# Placa_CLP_2021-08-01_15-29-45.net
KiCad netlist of a schematic drawn in EasyEDA
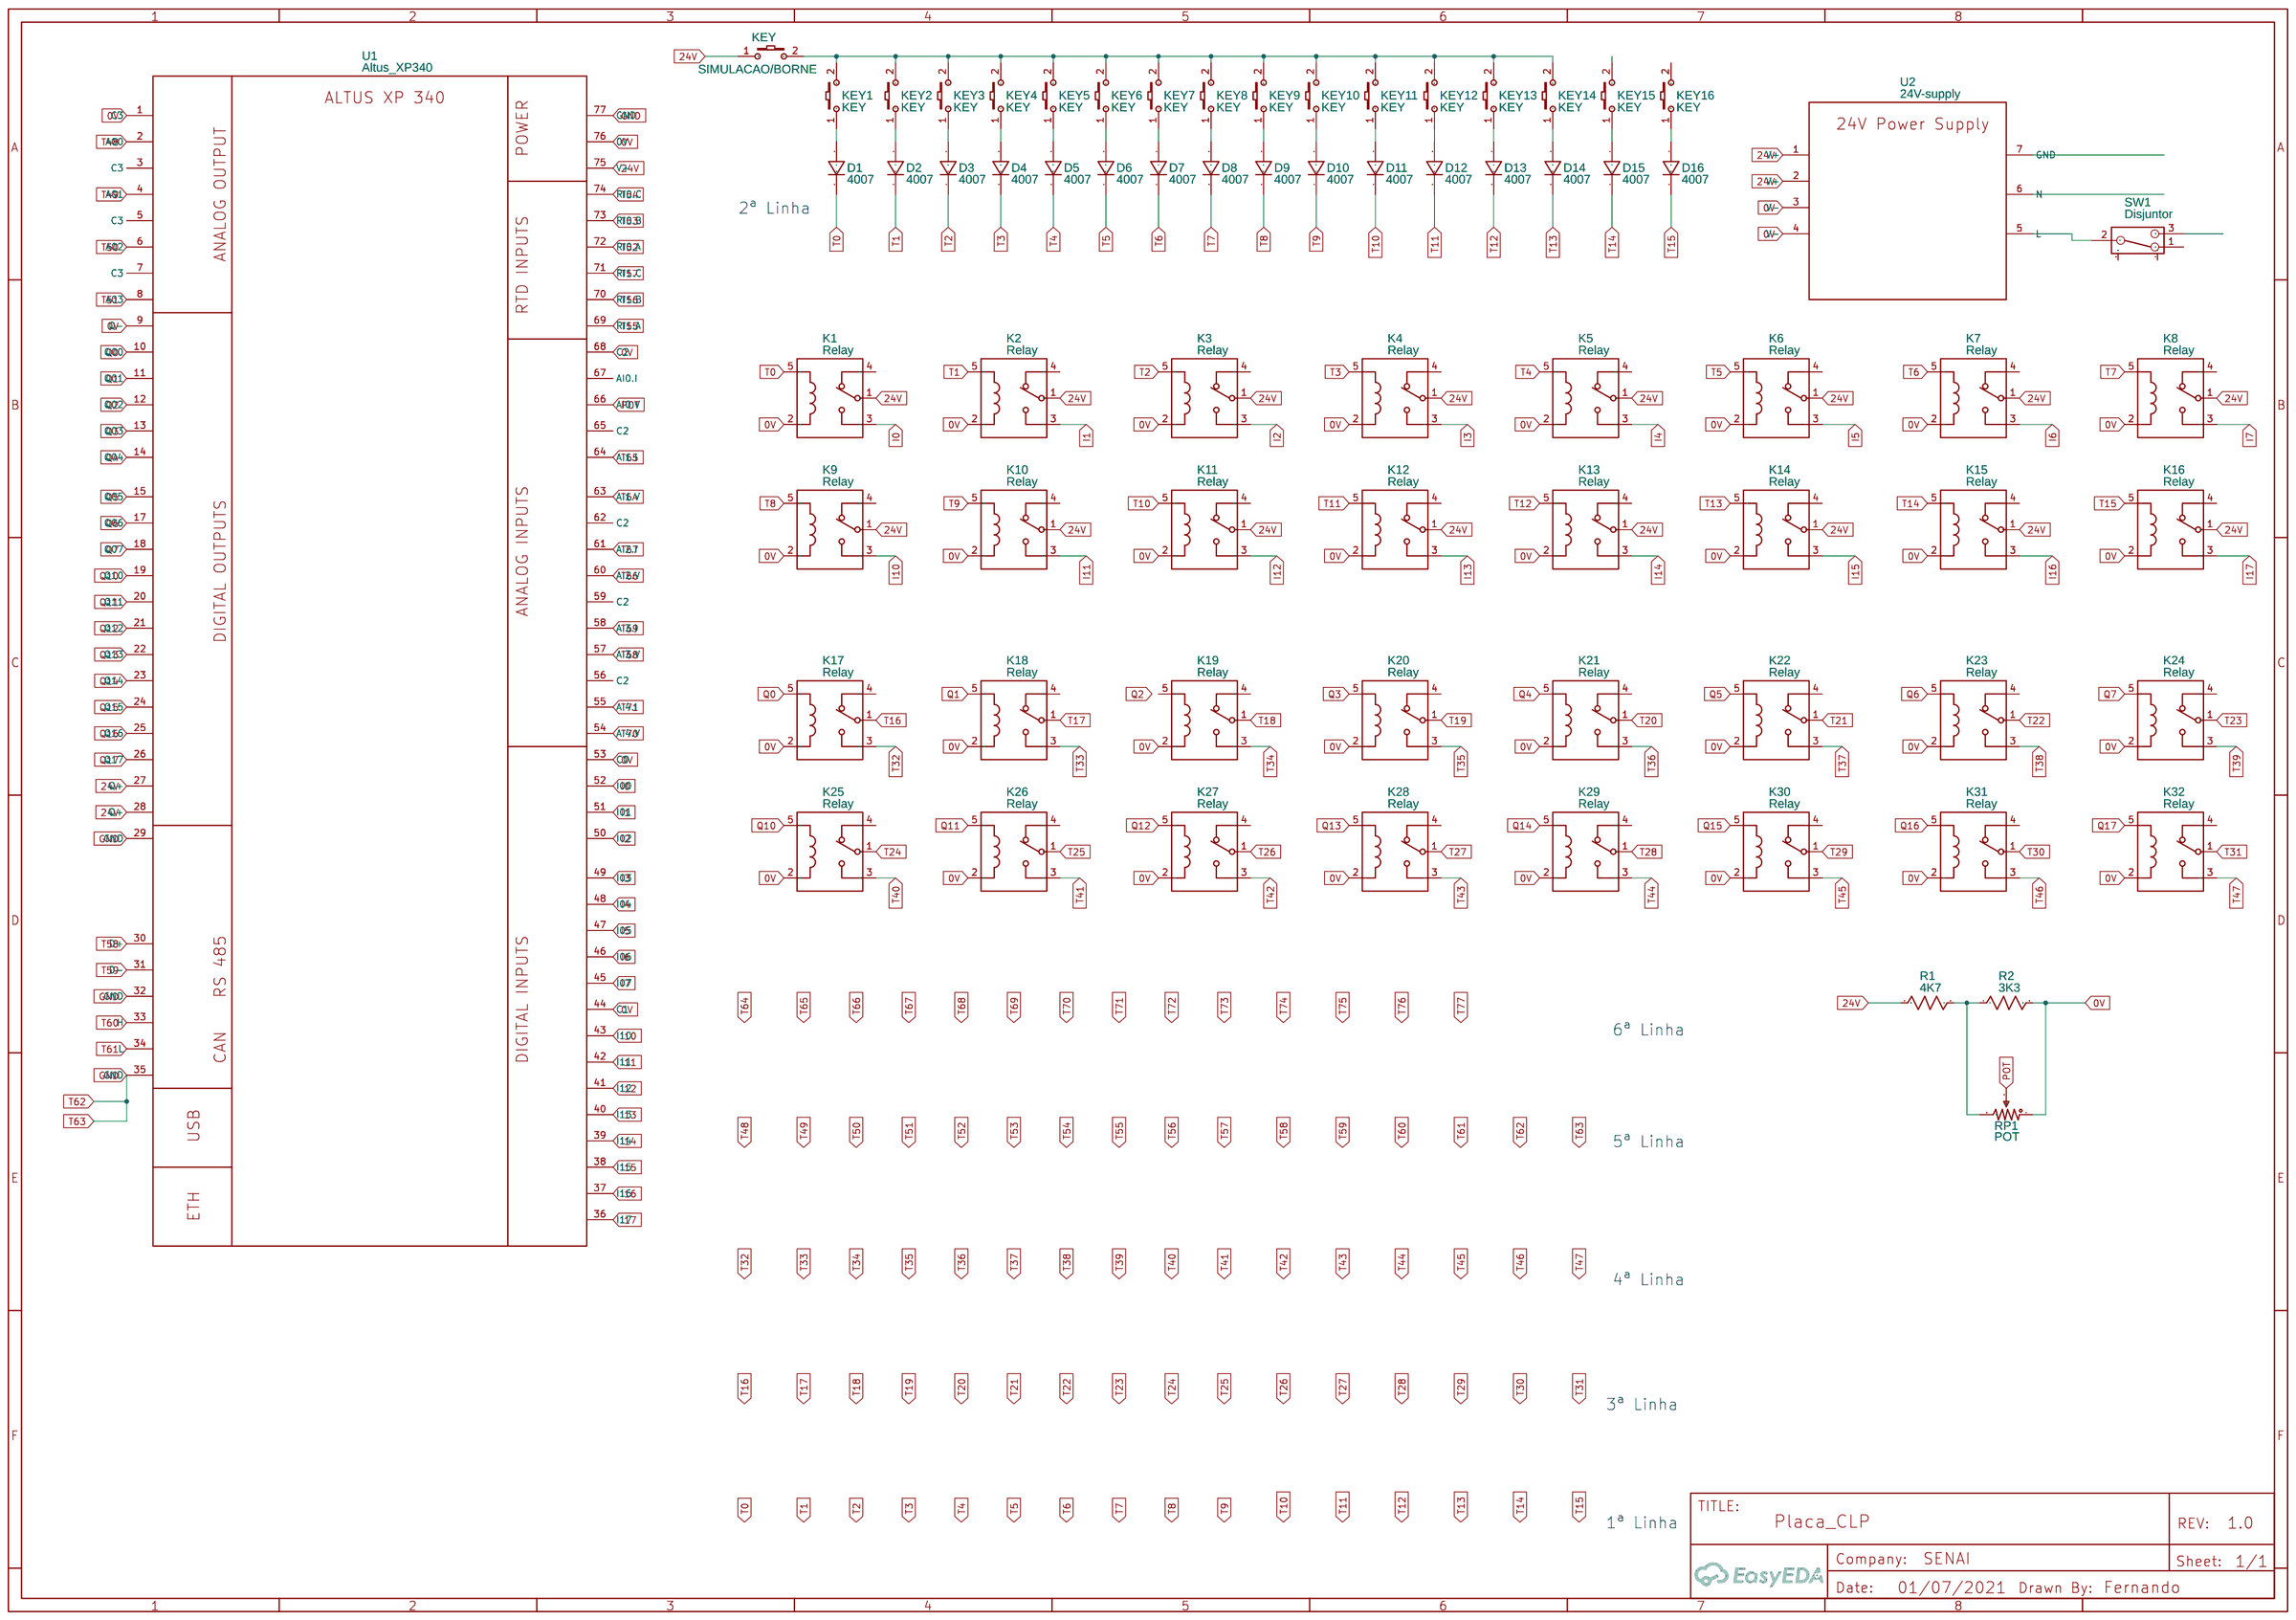
[diagram p0: schematic sheet]

(export (version "E")
  (design (tool "Eeschema 10.0.6"))
  (components
    (comp (ref "D1")
      (value "4007")
      (fields (field (name "BOM_Manufacturer Part") "1N4007") (field (name "BOM_Supplier Part") "C106903"))
      (libsource (lib "") (part "1N4007"))
    )
    (comp (ref "D2")
      (value "4007")
      (fields (field (name "BOM_Manufacturer Part") "1N4007") (field (name "BOM_Supplier Part") "C106903"))
      (libsource (lib "") (part "1N4007"))
    )
    (comp (ref "D3")
      (value "4007")
      (fields (field (name "BOM_Manufacturer Part") "1N4007") (field (name "BOM_Supplier Part") "C106903"))
      (libsource (lib "") (part "1N4007"))
    )
    (comp (ref "D4")
      (value "4007")
      (fields (field (name "BOM_Manufacturer Part") "1N4007") (field (name "BOM_Supplier Part") "C106903"))
      (libsource (lib "") (part "1N4007"))
    )
    (comp (ref "D5")
      (value "4007")
      (fields (field (name "BOM_Manufacturer Part") "1N4007") (field (name "BOM_Supplier Part") "C106903"))
      (libsource (lib "") (part "1N4007"))
    )
    (comp (ref "D6")
      (value "4007")
      (fields (field (name "BOM_Manufacturer Part") "1N4007") (field (name "BOM_Supplier Part") "C106903"))
      (libsource (lib "") (part "1N4007"))
    )
    (comp (ref "D7")
      (value "4007")
      (fields (field (name "BOM_Manufacturer Part") "1N4007") (field (name "BOM_Supplier Part") "C106903"))
      (libsource (lib "") (part "1N4007"))
    )
    (comp (ref "D8")
      (value "4007")
      (fields (field (name "BOM_Manufacturer Part") "1N4007") (field (name "BOM_Supplier Part") "C106903"))
      (libsource (lib "") (part "1N4007"))
    )
    (comp (ref "D9")
      (value "4007")
      (fields (field (name "BOM_Manufacturer Part") "1N4007") (field (name "BOM_Supplier Part") "C106903"))
      (libsource (lib "") (part "1N4007"))
    )
    (comp (ref "D10")
      (value "4007")
      (fields (field (name "BOM_Manufacturer Part") "1N4007") (field (name "BOM_Supplier Part") "C106903"))
      (libsource (lib "") (part "1N4007"))
    )
    (comp (ref "D11")
      (value "4007")
      (fields (field (name "BOM_Manufacturer Part") "1N4007") (field (name "BOM_Supplier Part") "C106903"))
      (libsource (lib "") (part "1N4007"))
    )
    (comp (ref "D12")
      (value "4007")
      (fields (field (name "BOM_Manufacturer Part") "1N4007") (field (name "BOM_Supplier Part") "C106903"))
      (libsource (lib "") (part "1N4007"))
    )
    (comp (ref "D13")
      (value "4007")
      (fields (field (name "BOM_Manufacturer Part") "1N4007") (field (name "BOM_Supplier Part") "C106903"))
      (libsource (lib "") (part "1N4007"))
    )
    (comp (ref "D14")
      (value "4007")
      (fields (field (name "BOM_Manufacturer Part") "1N4007") (field (name "BOM_Supplier Part") "C106903"))
      (libsource (lib "") (part "1N4007"))
    )
    (comp (ref "D15")
      (value "4007")
      (fields (field (name "BOM_Manufacturer Part") "1N4007") (field (name "BOM_Supplier Part") "C106903"))
      (libsource (lib "") (part "1N4007"))
    )
    (comp (ref "D16")
      (value "4007")
      (fields (field (name "BOM_Manufacturer Part") "1N4007") (field (name "BOM_Supplier Part") "C106903"))
      (libsource (lib "") (part "1N4007"))
    )
    (comp (ref "K1")
      (value "Relay")
      (fields
        (field (name "BOM_Manufacturer Part") "RelayHT3F-12VDC-SHG")
        (field (name "BOM_Supplier Part") "C22022")
      )
      (libsource (lib "") (part "RelayHT3F-12VDC-SHG"))
    )
    (comp (ref "K2")
      (value "Relay")
      (fields
        (field (name "BOM_Manufacturer Part") "RelayHT3F-12VDC-SHG")
        (field (name "BOM_Supplier Part") "C22022")
      )
      (libsource (lib "") (part "RelayHT3F-12VDC-SHG"))
    )
    (comp (ref "K3")
      (value "Relay")
      (fields
        (field (name "BOM_Manufacturer Part") "RelayHT3F-12VDC-SHG")
        (field (name "BOM_Supplier Part") "C22022")
      )
      (libsource (lib "") (part "RelayHT3F-12VDC-SHG"))
    )
    (comp (ref "K4")
      (value "Relay")
      (fields
        (field (name "BOM_Manufacturer Part") "RelayHT3F-12VDC-SHG")
        (field (name "BOM_Supplier Part") "C22022")
      )
      (libsource (lib "") (part "RelayHT3F-12VDC-SHG"))
    )
    (comp (ref "K5")
      (value "Relay")
      (fields
        (field (name "BOM_Manufacturer Part") "RelayHT3F-12VDC-SHG")
        (field (name "BOM_Supplier Part") "C22022")
      )
      (libsource (lib "") (part "RelayHT3F-12VDC-SHG"))
    )
    (comp (ref "K6")
      (value "Relay")
      (fields
        (field (name "BOM_Manufacturer Part") "RelayHT3F-12VDC-SHG")
        (field (name "BOM_Supplier Part") "C22022")
      )
      (libsource (lib "") (part "RelayHT3F-12VDC-SHG"))
    )
    (comp (ref "K7")
      (value "Relay")
      (fields
        (field (name "BOM_Manufacturer Part") "RelayHT3F-12VDC-SHG")
        (field (name "BOM_Supplier Part") "C22022")
      )
      (libsource (lib "") (part "RelayHT3F-12VDC-SHG"))
    )
    (comp (ref "K8")
      (value "Relay")
      (fields
        (field (name "BOM_Manufacturer Part") "RelayHT3F-12VDC-SHG")
        (field (name "BOM_Supplier Part") "C22022")
      )
      (libsource (lib "") (part "RelayHT3F-12VDC-SHG"))
    )
    (comp (ref "K9")
      (value "Relay")
      (fields
        (field (name "BOM_Manufacturer Part") "RelayHT3F-12VDC-SHG")
        (field (name "BOM_Supplier Part") "C22022")
      )
      (libsource (lib "") (part "RelayHT3F-12VDC-SHG"))
    )
    (comp (ref "K10")
      (value "Relay")
      (fields
        (field (name "BOM_Manufacturer Part") "RelayHT3F-12VDC-SHG")
        (field (name "BOM_Supplier Part") "C22022")
      )
      (libsource (lib "") (part "RelayHT3F-12VDC-SHG"))
    )
    (comp (ref "K11")
      (value "Relay")
      (fields
        (field (name "BOM_Manufacturer Part") "RelayHT3F-12VDC-SHG")
        (field (name "BOM_Supplier Part") "C22022")
      )
      (libsource (lib "") (part "RelayHT3F-12VDC-SHG"))
    )
    (comp (ref "K12")
      (value "Relay")
      (fields
        (field (name "BOM_Manufacturer Part") "RelayHT3F-12VDC-SHG")
        (field (name "BOM_Supplier Part") "C22022")
      )
      (libsource (lib "") (part "RelayHT3F-12VDC-SHG"))
    )
    (comp (ref "K13")
      (value "Relay")
      (fields
        (field (name "BOM_Manufacturer Part") "RelayHT3F-12VDC-SHG")
        (field (name "BOM_Supplier Part") "C22022")
      )
      (libsource (lib "") (part "RelayHT3F-12VDC-SHG"))
    )
    (comp (ref "K14")
      (value "Relay")
      (fields
        (field (name "BOM_Manufacturer Part") "RelayHT3F-12VDC-SHG")
        (field (name "BOM_Supplier Part") "C22022")
      )
      (libsource (lib "") (part "RelayHT3F-12VDC-SHG"))
    )
    (comp (ref "K15")
      (value "Relay")
      (fields
        (field (name "BOM_Manufacturer Part") "RelayHT3F-12VDC-SHG")
        (field (name "BOM_Supplier Part") "C22022")
      )
      (libsource (lib "") (part "RelayHT3F-12VDC-SHG"))
    )
    (comp (ref "K16")
      (value "Relay")
      (fields
        (field (name "BOM_Manufacturer Part") "RelayHT3F-12VDC-SHG")
        (field (name "BOM_Supplier Part") "C22022")
      )
      (libsource (lib "") (part "RelayHT3F-12VDC-SHG"))
    )
    (comp (ref "K17")
      (value "Relay")
      (fields
        (field (name "BOM_Manufacturer Part") "RelayHT3F-12VDC-SHG")
        (field (name "BOM_Supplier Part") "C22022")
      )
      (libsource (lib "") (part "RelayHT3F-12VDC-SHG"))
    )
    (comp (ref "K18")
      (value "Relay")
      (fields
        (field (name "BOM_Manufacturer Part") "RelayHT3F-12VDC-SHG")
        (field (name "BOM_Supplier Part") "C22022")
      )
      (libsource (lib "") (part "RelayHT3F-12VDC-SHG"))
    )
    (comp (ref "K19")
      (value "Relay")
      (fields
        (field (name "BOM_Manufacturer Part") "RelayHT3F-12VDC-SHG")
        (field (name "BOM_Supplier Part") "C22022")
      )
      (libsource (lib "") (part "RelayHT3F-12VDC-SHG"))
    )
    (comp (ref "K20")
      (value "Relay")
      (fields
        (field (name "BOM_Manufacturer Part") "RelayHT3F-12VDC-SHG")
        (field (name "BOM_Supplier Part") "C22022")
      )
      (libsource (lib "") (part "RelayHT3F-12VDC-SHG"))
    )
    (comp (ref "K21")
      (value "Relay")
      (fields
        (field (name "BOM_Manufacturer Part") "RelayHT3F-12VDC-SHG")
        (field (name "BOM_Supplier Part") "C22022")
      )
      (libsource (lib "") (part "RelayHT3F-12VDC-SHG"))
    )
    (comp (ref "K22")
      (value "Relay")
      (fields
        (field (name "BOM_Manufacturer Part") "RelayHT3F-12VDC-SHG")
        (field (name "BOM_Supplier Part") "C22022")
      )
      (libsource (lib "") (part "RelayHT3F-12VDC-SHG"))
    )
    (comp (ref "K23")
      (value "Relay")
      (fields
        (field (name "BOM_Manufacturer Part") "RelayHT3F-12VDC-SHG")
        (field (name "BOM_Supplier Part") "C22022")
      )
      (libsource (lib "") (part "RelayHT3F-12VDC-SHG"))
    )
    (comp (ref "K24")
      (value "Relay")
      (fields
        (field (name "BOM_Manufacturer Part") "RelayHT3F-12VDC-SHG")
        (field (name "BOM_Supplier Part") "C22022")
      )
      (libsource (lib "") (part "RelayHT3F-12VDC-SHG"))
    )
    (comp (ref "K25")
      (value "Relay")
      (fields
        (field (name "BOM_Manufacturer Part") "RelayHT3F-12VDC-SHG")
        (field (name "BOM_Supplier Part") "C22022")
      )
      (libsource (lib "") (part "RelayHT3F-12VDC-SHG"))
    )
    (comp (ref "K26")
      (value "Relay")
      (fields
        (field (name "BOM_Manufacturer Part") "RelayHT3F-12VDC-SHG")
        (field (name "BOM_Supplier Part") "C22022")
      )
      (libsource (lib "") (part "RelayHT3F-12VDC-SHG"))
    )
    (comp (ref "K27")
      (value "Relay")
      (fields
        (field (name "BOM_Manufacturer Part") "RelayHT3F-12VDC-SHG")
        (field (name "BOM_Supplier Part") "C22022")
      )
      (libsource (lib "") (part "RelayHT3F-12VDC-SHG"))
    )
    (comp (ref "K28")
      (value "Relay")
      (fields
        (field (name "BOM_Manufacturer Part") "RelayHT3F-12VDC-SHG")
        (field (name "BOM_Supplier Part") "C22022")
      )
      (libsource (lib "") (part "RelayHT3F-12VDC-SHG"))
    )
    (comp (ref "K29")
      (value "Relay")
      (fields
        (field (name "BOM_Manufacturer Part") "RelayHT3F-12VDC-SHG")
        (field (name "BOM_Supplier Part") "C22022")
      )
      (libsource (lib "") (part "RelayHT3F-12VDC-SHG"))
    )
    (comp (ref "K30")
      (value "Relay")
      (fields
        (field (name "BOM_Manufacturer Part") "RelayHT3F-12VDC-SHG")
        (field (name "BOM_Supplier Part") "C22022")
      )
      (libsource (lib "") (part "RelayHT3F-12VDC-SHG"))
    )
    (comp (ref "K31")
      (value "Relay")
      (fields
        (field (name "BOM_Manufacturer Part") "RelayHT3F-12VDC-SHG")
        (field (name "BOM_Supplier Part") "C22022")
      )
      (libsource (lib "") (part "RelayHT3F-12VDC-SHG"))
    )
    (comp (ref "K32")
      (value "Relay")
      (fields
        (field (name "BOM_Manufacturer Part") "RelayHT3F-12VDC-SHG")
        (field (name "BOM_Supplier Part") "C22022")
      )
      (libsource (lib "") (part "RelayHT3F-12VDC-SHG"))
    )
    (comp (ref "KEY1")
      (value "KEY")
      (fields
        (field (name "BOM_Manufacturer Part") "K2-1107ST-A4SW-06")
        (field (name "BOM_Supplier Part") "C118141")
      )
      (libsource (lib "") (part "K2-3.6×6.1_SMD_1"))
    )
    (comp (ref "KEY2")
      (value "KEY")
      (fields
        (field (name "BOM_Manufacturer Part") "K2-1107ST-A4SW-06")
        (field (name "BOM_Supplier Part") "C118141")
      )
      (libsource (lib "") (part "K2-3.6×6.1_SMD_1"))
    )
    (comp (ref "KEY3")
      (value "KEY")
      (fields
        (field (name "BOM_Manufacturer Part") "K2-1107ST-A4SW-06")
        (field (name "BOM_Supplier Part") "C118141")
      )
      (libsource (lib "") (part "K2-3.6×6.1_SMD_1"))
    )
    (comp (ref "KEY4")
      (value "KEY")
      (fields
        (field (name "BOM_Manufacturer Part") "K2-1107ST-A4SW-06")
        (field (name "BOM_Supplier Part") "C118141")
      )
      (libsource (lib "") (part "K2-3.6×6.1_SMD_1"))
    )
    (comp (ref "KEY5")
      (value "KEY")
      (fields
        (field (name "BOM_Manufacturer Part") "K2-1107ST-A4SW-06")
        (field (name "BOM_Supplier Part") "C118141")
      )
      (libsource (lib "") (part "K2-3.6×6.1_SMD_1"))
    )
    (comp (ref "KEY6")
      (value "KEY")
      (fields
        (field (name "BOM_Manufacturer Part") "K2-1107ST-A4SW-06")
        (field (name "BOM_Supplier Part") "C118141")
      )
      (libsource (lib "") (part "K2-3.6×6.1_SMD_1"))
    )
    (comp (ref "KEY7")
      (value "KEY")
      (fields
        (field (name "BOM_Manufacturer Part") "K2-1107ST-A4SW-06")
        (field (name "BOM_Supplier Part") "C118141")
      )
      (libsource (lib "") (part "K2-3.6×6.1_SMD_1"))
    )
    (comp (ref "KEY8")
      (value "KEY")
      (fields
        (field (name "BOM_Manufacturer Part") "K2-1107ST-A4SW-06")
        (field (name "BOM_Supplier Part") "C118141")
      )
      (libsource (lib "") (part "K2-3.6×6.1_SMD_1"))
    )
    (comp (ref "KEY9")
      (value "KEY")
      (fields
        (field (name "BOM_Manufacturer Part") "K2-1107ST-A4SW-06")
        (field (name "BOM_Supplier Part") "C118141")
      )
      (libsource (lib "") (part "K2-3.6×6.1_SMD_1"))
    )
    (comp (ref "KEY10")
      (value "KEY")
      (fields
        (field (name "BOM_Manufacturer Part") "K2-1107ST-A4SW-06")
        (field (name "BOM_Supplier Part") "C118141")
      )
      (libsource (lib "") (part "K2-3.6×6.1_SMD_1"))
    )
    (comp (ref "KEY11")
      (value "KEY")
      (fields
        (field (name "BOM_Manufacturer Part") "K2-1107ST-A4SW-06")
        (field (name "BOM_Supplier Part") "C118141")
      )
      (libsource (lib "") (part "K2-3.6×6.1_SMD_1"))
    )
    (comp (ref "KEY12")
      (value "KEY")
      (fields
        (field (name "BOM_Manufacturer Part") "K2-1107ST-A4SW-06")
        (field (name "BOM_Supplier Part") "C118141")
      )
      (libsource (lib "") (part "K2-3.6×6.1_SMD_1"))
    )
    (comp (ref "KEY13")
      (value "KEY")
      (fields
        (field (name "BOM_Manufacturer Part") "K2-1107ST-A4SW-06")
        (field (name "BOM_Supplier Part") "C118141")
      )
      (libsource (lib "") (part "K2-3.6×6.1_SMD_1"))
    )
    (comp (ref "KEY14")
      (value "KEY")
      (fields
        (field (name "BOM_Manufacturer Part") "K2-1107ST-A4SW-06")
        (field (name "BOM_Supplier Part") "C118141")
      )
      (libsource (lib "") (part "K2-3.6×6.1_SMD_1"))
    )
    (comp (ref "KEY15")
      (value "KEY")
      (fields
        (field (name "BOM_Manufacturer Part") "K2-1107ST-A4SW-06")
        (field (name "BOM_Supplier Part") "C118141")
      )
      (libsource (lib "") (part "K2-3.6×6.1_SMD_1"))
    )
    (comp (ref "KEY16")
      (value "KEY")
      (fields
        (field (name "BOM_Manufacturer Part") "K2-1107ST-A4SW-06")
        (field (name "BOM_Supplier Part") "C118141")
      )
      (libsource (lib "") (part "K2-3.6×6.1_SMD_1"))
    )
    (comp (ref "R1") (value "4K7") (libsource (lib "") (part "R_0603_US")))
    (comp (ref "R2") (value "3K3") (libsource (lib "") (part "R_0603_US")))
    (comp (ref "RP1") (value "POT") (libsource (lib "") (part "R_3386P_US")))
    (comp (ref "SIMULACAO/BORNE")
      (value "KEY")
      (fields
        (field (name "BOM_Manufacturer Part") "K2-1107ST-A4SW-06")
        (field (name "BOM_Supplier Part") "C118141")
      )
      (libsource (lib "") (part "K2-3.6×6.1_SMD"))
    )
    (comp (ref "SW1")
      (value "Disjuntor")
      (fields
        (field (name "BOM_Manufacturer Part") "SK-12D02-VG5")
        (field (name "BOM_Supplier Part") "C136722")
      )
      (libsource (lib "") (part "SK-12D02-VG5"))
    )
    (comp (ref "U1") (value "Altus_XP340") (libsource (lib "") (part "Altus_XP340")))
    (comp (ref "U2") (value "24V-supply") (libsource (lib "") (part "24V-supply")))
  )
  (nets
    (net (code "1") (name "0V") (class "Default")
      (node (ref "K1") (pin "2") (pinfunction "2_2") (pintype "unspecified"))
      (node (ref "K10") (pin "2") (pinfunction "2_2") (pintype "unspecified"))
      (node (ref "K11") (pin "2") (pinfunction "2_2") (pintype "unspecified"))
      (node (ref "K12") (pin "2") (pinfunction "2_2") (pintype "unspecified"))
      (node (ref "K13") (pin "2") (pinfunction "2_2") (pintype "unspecified"))
      (node (ref "K14") (pin "2") (pinfunction "2_2") (pintype "unspecified"))
      (node (ref "K15") (pin "2") (pinfunction "2_2") (pintype "unspecified"))
      (node (ref "K16") (pin "2") (pinfunction "2_2") (pintype "unspecified"))
      (node (ref "K17") (pin "2") (pinfunction "2_2") (pintype "unspecified"))
      (node (ref "K18") (pin "2") (pinfunction "2_2") (pintype "unspecified"))
      (node (ref "K19") (pin "2") (pinfunction "2_2") (pintype "unspecified"))
      (node (ref "K2") (pin "2") (pinfunction "2_2") (pintype "unspecified"))
      (node (ref "K20") (pin "2") (pinfunction "2_2") (pintype "unspecified"))
      (node (ref "K21") (pin "2") (pinfunction "2_2") (pintype "unspecified"))
      (node (ref "K22") (pin "2") (pinfunction "2_2") (pintype "unspecified"))
      (node (ref "K23") (pin "2") (pinfunction "2_2") (pintype "unspecified"))
      (node (ref "K24") (pin "2") (pinfunction "2_2") (pintype "unspecified"))
      (node (ref "K25") (pin "2") (pinfunction "2_2") (pintype "unspecified"))
      (node (ref "K26") (pin "2") (pinfunction "2_2") (pintype "unspecified"))
      (node (ref "K27") (pin "2") (pinfunction "2_2") (pintype "unspecified"))
      (node (ref "K28") (pin "2") (pinfunction "2_2") (pintype "unspecified"))
      (node (ref "K29") (pin "2") (pinfunction "2_2") (pintype "unspecified"))
      (node (ref "K3") (pin "2") (pinfunction "2_2") (pintype "unspecified"))
      (node (ref "K30") (pin "2") (pinfunction "2_2") (pintype "unspecified"))
      (node (ref "K31") (pin "2") (pinfunction "2_2") (pintype "unspecified"))
      (node (ref "K32") (pin "2") (pinfunction "2_2") (pintype "unspecified"))
      (node (ref "K4") (pin "2") (pinfunction "2_2") (pintype "unspecified"))
      (node (ref "K5") (pin "2") (pinfunction "2_2") (pintype "unspecified"))
      (node (ref "K6") (pin "2") (pinfunction "2_2") (pintype "unspecified"))
      (node (ref "K7") (pin "2") (pinfunction "2_2") (pintype "unspecified"))
      (node (ref "K8") (pin "2") (pinfunction "2_2") (pintype "unspecified"))
      (node (ref "K9") (pin "2") (pinfunction "2_2") (pintype "unspecified"))
      (node (ref "R2") (pin "2") (pinfunction "2_2") (pintype "unspecified"))
      (node (ref "RP1") (pin "1") (pinfunction "1_1") (pintype "unspecified"))
    )
    (net (code "2") (name "24V") (class "Default")
      (node (ref "K1") (pin "1") (pinfunction "1_1") (pintype "unspecified"))
      (node (ref "K10") (pin "1") (pinfunction "1_1") (pintype "unspecified"))
      (node (ref "K11") (pin "1") (pinfunction "1_1") (pintype "unspecified"))
      (node (ref "K12") (pin "1") (pinfunction "1_1") (pintype "unspecified"))
      (node (ref "K13") (pin "1") (pinfunction "1_1") (pintype "unspecified"))
      (node (ref "K14") (pin "1") (pinfunction "1_1") (pintype "unspecified"))
      (node (ref "K15") (pin "1") (pinfunction "1_1") (pintype "unspecified"))
      (node (ref "K16") (pin "1") (pinfunction "1_1") (pintype "unspecified"))
      (node (ref "K2") (pin "1") (pinfunction "1_1") (pintype "unspecified"))
      (node (ref "K3") (pin "1") (pinfunction "1_1") (pintype "unspecified"))
      (node (ref "K4") (pin "1") (pinfunction "1_1") (pintype "unspecified"))
      (node (ref "K5") (pin "1") (pinfunction "1_1") (pintype "unspecified"))
      (node (ref "K6") (pin "1") (pinfunction "1_1") (pintype "unspecified"))
      (node (ref "K7") (pin "1") (pinfunction "1_1") (pintype "unspecified"))
      (node (ref "K8") (pin "1") (pinfunction "1_1") (pintype "unspecified"))
      (node (ref "K9") (pin "1") (pinfunction "1_1") (pintype "unspecified"))
      (node (ref "R1") (pin "1") (pinfunction "1_1") (pintype "unspecified"))
      (node (ref "SIMULACAO/BORNE") (pin "1") (pinfunction "1_1") (pintype "unspecified"))
    )
    (net (code "4") (name "I0") (class "Default")
      (node (ref "K1") (pin "3") (pinfunction "3_3") (pintype "unspecified"))
    )
    (net (code "5") (name "I1") (class "Default")
      (node (ref "K2") (pin "3") (pinfunction "3_3") (pintype "unspecified"))
    )
    (net (code "6") (name "I2") (class "Default")
      (node (ref "K3") (pin "3") (pinfunction "3_3") (pintype "unspecified"))
    )
    (net (code "7") (name "I3") (class "Default")
      (node (ref "K4") (pin "3") (pinfunction "3_3") (pintype "unspecified"))
    )
    (net (code "8") (name "I4") (class "Default")
      (node (ref "K5") (pin "3") (pinfunction "3_3") (pintype "unspecified"))
    )
    (net (code "9") (name "I5") (class "Default")
      (node (ref "K6") (pin "3") (pinfunction "3_3") (pintype "unspecified"))
    )
    (net (code "10") (name "I6") (class "Default")
      (node (ref "K7") (pin "3") (pinfunction "3_3") (pintype "unspecified"))
    )
    (net (code "11") (name "I7") (class "Default")
      (node (ref "K8") (pin "3") (pinfunction "3_3") (pintype "unspecified"))
    )
    (net (code "12") (name "I10") (class "Default")
      (node (ref "K9") (pin "3") (pinfunction "3_3") (pintype "unspecified"))
    )
    (net (code "13") (name "I11") (class "Default")
      (node (ref "K10") (pin "3") (pinfunction "3_3") (pintype "unspecified"))
    )
    (net (code "14") (name "I12") (class "Default")
      (node (ref "K11") (pin "3") (pinfunction "3_3") (pintype "unspecified"))
    )
    (net (code "15") (name "I13") (class "Default")
      (node (ref "K12") (pin "3") (pinfunction "3_3") (pintype "unspecified"))
    )
    (net (code "16") (name "I14") (class "Default")
      (node (ref "K13") (pin "3") (pinfunction "3_3") (pintype "unspecified"))
    )
    (net (code "17") (name "I15") (class "Default")
      (node (ref "K14") (pin "3") (pinfunction "3_3") (pintype "unspecified"))
    )
    (net (code "18") (name "I16") (class "Default")
      (node (ref "K15") (pin "3") (pinfunction "3_3") (pintype "unspecified"))
    )
    (net (code "19") (name "I17") (class "Default")
      (node (ref "K16") (pin "3") (pinfunction "3_3") (pintype "unspecified"))
    )
    (net (code "20") (name "Net-(D1-Pad2)") (class "Default")
      (node (ref "D1") (pin "2") (pinfunction "2_2") (pintype "unspecified"))
      (node (ref "KEY1") (pin "1") (pinfunction "1_1") (pintype "unspecified"))
    )
    (net (code "21") (name "Net-(D2-Pad2)") (class "Default")
      (node (ref "D2") (pin "2") (pinfunction "2_2") (pintype "unspecified"))
      (node (ref "KEY2") (pin "1") (pinfunction "1_1") (pintype "unspecified"))
    )
    (net (code "22") (name "Net-(D3-Pad2)") (class "Default")
      (node (ref "D3") (pin "2") (pinfunction "2_2") (pintype "unspecified"))
      (node (ref "KEY3") (pin "1") (pinfunction "1_1") (pintype "unspecified"))
    )
    (net (code "23") (name "Net-(D4-Pad2)") (class "Default")
      (node (ref "D4") (pin "2") (pinfunction "2_2") (pintype "unspecified"))
      (node (ref "KEY4") (pin "1") (pinfunction "1_1") (pintype "unspecified"))
    )
    (net (code "24") (name "Net-(D5-Pad2)") (class "Default")
      (node (ref "D5") (pin "2") (pinfunction "2_2") (pintype "unspecified"))
      (node (ref "KEY5") (pin "1") (pinfunction "1_1") (pintype "unspecified"))
    )
    (net (code "25") (name "Net-(D6-Pad2)") (class "Default")
      (node (ref "D6") (pin "2") (pinfunction "2_2") (pintype "unspecified"))
      (node (ref "KEY6") (pin "1") (pinfunction "1_1") (pintype "unspecified"))
    )
    (net (code "26") (name "Net-(D7-Pad2)") (class "Default")
      (node (ref "D7") (pin "2") (pinfunction "2_2") (pintype "unspecified"))
      (node (ref "KEY7") (pin "1") (pinfunction "1_1") (pintype "unspecified"))
    )
    (net (code "27") (name "Net-(D8-Pad2)") (class "Default")
      (node (ref "D8") (pin "2") (pinfunction "2_2") (pintype "unspecified"))
      (node (ref "KEY8") (pin "1") (pinfunction "1_1") (pintype "unspecified"))
    )
    (net (code "28") (name "Net-(D9-Pad2)") (class "Default")
      (node (ref "D9") (pin "2") (pinfunction "2_2") (pintype "unspecified"))
      (node (ref "KEY9") (pin "1") (pinfunction "1_1") (pintype "unspecified"))
    )
    (net (code "29") (name "Net-(D10-Pad2)") (class "Default")
      (node (ref "D10") (pin "2") (pinfunction "2_2") (pintype "unspecified"))
      (node (ref "KEY10") (pin "1") (pinfunction "1_1") (pintype "unspecified"))
    )
    (net (code "30") (name "Net-(D11-Pad2)") (class "Default")
      (node (ref "D11") (pin "2") (pinfunction "2_2") (pintype "unspecified"))
      (node (ref "KEY11") (pin "1") (pinfunction "1_1") (pintype "unspecified"))
    )
    (net (code "31") (name "Net-(D12-Pad2)") (class "Default")
      (node (ref "D12") (pin "2") (pinfunction "2_2") (pintype "unspecified"))
      (node (ref "KEY12") (pin "1") (pinfunction "1_1") (pintype "unspecified"))
    )
    (net (code "32") (name "Net-(D13-Pad2)") (class "Default")
      (node (ref "D13") (pin "2") (pinfunction "2_2") (pintype "unspecified"))
      (node (ref "KEY13") (pin "1") (pinfunction "1_1") (pintype "unspecified"))
    )
    (net (code "33") (name "Net-(D14-Pad2)") (class "Default")
      (node (ref "D14") (pin "2") (pinfunction "2_2") (pintype "unspecified"))
      (node (ref "KEY14") (pin "1") (pinfunction "1_1") (pintype "unspecified"))
    )
    (net (code "34") (name "Net-(D15-Pad2)") (class "Default")
      (node (ref "D15") (pin "2") (pinfunction "2_2") (pintype "unspecified"))
      (node (ref "KEY15") (pin "1") (pinfunction "1_1") (pintype "unspecified"))
    )
    (net (code "35") (name "Net-(D16-Pad2)") (class "Default")
      (node (ref "D16") (pin "2") (pinfunction "2_2") (pintype "unspecified"))
      (node (ref "KEY16") (pin "1") (pinfunction "1_1") (pintype "unspecified"))
    )
    (net (code "36") (name "Net-(KEY1-Pad2)") (class "Default")
      (node (ref "KEY1") (pin "2") (pinfunction "2_2") (pintype "unspecified"))
      (node (ref "KEY10") (pin "2") (pinfunction "2_2") (pintype "unspecified"))
      (node (ref "KEY11") (pin "2") (pinfunction "2_2") (pintype "unspecified"))
      (node (ref "KEY12") (pin "2") (pinfunction "2_2") (pintype "unspecified"))
      (node (ref "KEY13") (pin "2") (pinfunction "2_2") (pintype "unspecified"))
      (node (ref "KEY14") (pin "2") (pinfunction "2_2") (pintype "unspecified"))
      (node (ref "KEY2") (pin "2") (pinfunction "2_2") (pintype "unspecified"))
      (node (ref "KEY3") (pin "2") (pinfunction "2_2") (pintype "unspecified"))
      (node (ref "KEY4") (pin "2") (pinfunction "2_2") (pintype "unspecified"))
      (node (ref "KEY5") (pin "2") (pinfunction "2_2") (pintype "unspecified"))
      (node (ref "KEY6") (pin "2") (pinfunction "2_2") (pintype "unspecified"))
      (node (ref "KEY7") (pin "2") (pinfunction "2_2") (pintype "unspecified"))
      (node (ref "KEY8") (pin "2") (pinfunction "2_2") (pintype "unspecified"))
      (node (ref "KEY9") (pin "2") (pinfunction "2_2") (pintype "unspecified"))
      (node (ref "SIMULACAO/BORNE") (pin "2") (pinfunction "2_2") (pintype "unspecified"))
    )
    (net (code "37") (name "Net-(R1-Pad2)") (class "Default")
      (node (ref "R1") (pin "2") (pinfunction "2_2") (pintype "unspecified"))
      (node (ref "R2") (pin "1") (pinfunction "1_1") (pintype "unspecified"))
      (node (ref "RP1") (pin "3") (pinfunction "3_3") (pintype "unspecified"))
    )
    (net (code "38") (name "POT") (class "Default")
      (node (ref "RP1") (pin "2") (pinfunction "2_2") (pintype "unspecified"))
    )
    (net (code "39") (name "Q0") (class "Default")
      (node (ref "K17") (pin "5") (pinfunction "5_5") (pintype "unspecified"))
    )
    (net (code "40") (name "Q1") (class "Default")
      (node (ref "K18") (pin "5") (pinfunction "5_5") (pintype "unspecified"))
    )
    (net (code "42") (name "Q3") (class "Default")
      (node (ref "K20") (pin "5") (pinfunction "5_5") (pintype "unspecified"))
    )
    (net (code "43") (name "Q4") (class "Default")
      (node (ref "K21") (pin "5") (pinfunction "5_5") (pintype "unspecified"))
    )
    (net (code "44") (name "Q5") (class "Default")
      (node (ref "K22") (pin "5") (pinfunction "5_5") (pintype "unspecified"))
    )
    (net (code "45") (name "Q6") (class "Default")
      (node (ref "K23") (pin "5") (pinfunction "5_5") (pintype "unspecified"))
    )
    (net (code "46") (name "Q7") (class "Default")
      (node (ref "K24") (pin "5") (pinfunction "5_5") (pintype "unspecified"))
    )
    (net (code "47") (name "Q10") (class "Default")
      (node (ref "K25") (pin "5") (pinfunction "5_5") (pintype "unspecified"))
    )
    (net (code "48") (name "Q11") (class "Default")
      (node (ref "K26") (pin "5") (pinfunction "5_5") (pintype "unspecified"))
    )
    (net (code "49") (name "Q12") (class "Default")
      (node (ref "K27") (pin "5") (pinfunction "5_5") (pintype "unspecified"))
    )
    (net (code "50") (name "Q13") (class "Default")
      (node (ref "K28") (pin "5") (pinfunction "5_5") (pintype "unspecified"))
    )
    (net (code "51") (name "Q14") (class "Default")
      (node (ref "K29") (pin "5") (pinfunction "5_5") (pintype "unspecified"))
    )
    (net (code "52") (name "Q15") (class "Default")
      (node (ref "K30") (pin "5") (pinfunction "5_5") (pintype "unspecified"))
    )
    (net (code "53") (name "Q16") (class "Default")
      (node (ref "K31") (pin "5") (pinfunction "5_5") (pintype "unspecified"))
    )
    (net (code "54") (name "Q17") (class "Default")
      (node (ref "K32") (pin "5") (pinfunction "5_5") (pintype "unspecified"))
    )
    (net (code "55") (name "T0") (class "Default")
      (node (ref "D1") (pin "1") (pinfunction "1_1") (pintype "unspecified"))
      (node (ref "K1") (pin "5") (pinfunction "5_5") (pintype "unspecified"))
    )
    (net (code "56") (name "T1") (class "Default")
      (node (ref "D2") (pin "1") (pinfunction "1_1") (pintype "unspecified"))
      (node (ref "K2") (pin "5") (pinfunction "5_5") (pintype "unspecified"))
    )
    (net (code "57") (name "T2") (class "Default")
      (node (ref "D3") (pin "1") (pinfunction "1_1") (pintype "unspecified"))
      (node (ref "K3") (pin "5") (pinfunction "5_5") (pintype "unspecified"))
    )
    (net (code "58") (name "T3") (class "Default")
      (node (ref "D4") (pin "1") (pinfunction "1_1") (pintype "unspecified"))
      (node (ref "K4") (pin "5") (pinfunction "5_5") (pintype "unspecified"))
    )
    (net (code "59") (name "T4") (class "Default")
      (node (ref "D5") (pin "1") (pinfunction "1_1") (pintype "unspecified"))
      (node (ref "K5") (pin "5") (pinfunction "5_5") (pintype "unspecified"))
    )
    (net (code "60") (name "T5") (class "Default")
      (node (ref "D6") (pin "1") (pinfunction "1_1") (pintype "unspecified"))
      (node (ref "K6") (pin "5") (pinfunction "5_5") (pintype "unspecified"))
    )
    (net (code "61") (name "T6") (class "Default")
      (node (ref "D7") (pin "1") (pinfunction "1_1") (pintype "unspecified"))
      (node (ref "K7") (pin "5") (pinfunction "5_5") (pintype "unspecified"))
    )
    (net (code "62") (name "T7") (class "Default")
      (node (ref "D8") (pin "1") (pinfunction "1_1") (pintype "unspecified"))
      (node (ref "K8") (pin "5") (pinfunction "5_5") (pintype "unspecified"))
    )
    (net (code "63") (name "T8") (class "Default")
      (node (ref "D9") (pin "1") (pinfunction "1_1") (pintype "unspecified"))
      (node (ref "K9") (pin "5") (pinfunction "5_5") (pintype "unspecified"))
    )
    (net (code "64") (name "T9") (class "Default")
      (node (ref "D10") (pin "1") (pinfunction "1_1") (pintype "unspecified"))
      (node (ref "K10") (pin "5") (pinfunction "5_5") (pintype "unspecified"))
    )
    (net (code "65") (name "T10") (class "Default")
      (node (ref "D11") (pin "1") (pinfunction "1_1") (pintype "unspecified"))
      (node (ref "K11") (pin "5") (pinfunction "5_5") (pintype "unspecified"))
    )
    (net (code "66") (name "T11") (class "Default")
      (node (ref "D12") (pin "1") (pinfunction "1_1") (pintype "unspecified"))
      (node (ref "K12") (pin "5") (pinfunction "5_5") (pintype "unspecified"))
    )
    (net (code "67") (name "T12") (class "Default")
      (node (ref "D13") (pin "1") (pinfunction "1_1") (pintype "unspecified"))
      (node (ref "K13") (pin "5") (pinfunction "5_5") (pintype "unspecified"))
    )
    (net (code "68") (name "T13") (class "Default")
      (node (ref "D14") (pin "1") (pinfunction "1_1") (pintype "unspecified"))
      (node (ref "K14") (pin "5") (pinfunction "5_5") (pintype "unspecified"))
    )
    (net (code "69") (name "T14") (class "Default")
      (node (ref "D15") (pin "1") (pinfunction "1_1") (pintype "unspecified"))
      (node (ref "K15") (pin "5") (pinfunction "5_5") (pintype "unspecified"))
    )
    (net (code "70") (name "T15") (class "Default")
      (node (ref "D16") (pin "1") (pinfunction "1_1") (pintype "unspecified"))
      (node (ref "K16") (pin "5") (pinfunction "5_5") (pintype "unspecified"))
    )
    (net (code "71") (name "T16") (class "Default")
      (node (ref "K17") (pin "1") (pinfunction "1_1") (pintype "unspecified"))
    )
    (net (code "72") (name "T17") (class "Default")
      (node (ref "K18") (pin "1") (pinfunction "1_1") (pintype "unspecified"))
    )
    (net (code "73") (name "T18") (class "Default")
      (node (ref "K19") (pin "1") (pinfunction "1_1") (pintype "unspecified"))
    )
    (net (code "74") (name "T19") (class "Default")
      (node (ref "K20") (pin "1") (pinfunction "1_1") (pintype "unspecified"))
    )
    (net (code "75") (name "T20") (class "Default")
      (node (ref "K21") (pin "1") (pinfunction "1_1") (pintype "unspecified"))
    )
    (net (code "76") (name "T21") (class "Default")
      (node (ref "K22") (pin "1") (pinfunction "1_1") (pintype "unspecified"))
    )
    (net (code "77") (name "T22") (class "Default")
      (node (ref "K23") (pin "1") (pinfunction "1_1") (pintype "unspecified"))
    )
    (net (code "78") (name "T23") (class "Default")
      (node (ref "K24") (pin "1") (pinfunction "1_1") (pintype "unspecified"))
    )
    (net (code "79") (name "T24") (class "Default")
      (node (ref "K25") (pin "1") (pinfunction "1_1") (pintype "unspecified"))
    )
    (net (code "80") (name "T25") (class "Default")
      (node (ref "K26") (pin "1") (pinfunction "1_1") (pintype "unspecified"))
    )
    (net (code "81") (name "T26") (class "Default")
      (node (ref "K27") (pin "1") (pinfunction "1_1") (pintype "unspecified"))
    )
    (net (code "82") (name "T27") (class "Default")
      (node (ref "K28") (pin "1") (pinfunction "1_1") (pintype "unspecified"))
    )
    (net (code "83") (name "T28") (class "Default")
      (node (ref "K29") (pin "1") (pinfunction "1_1") (pintype "unspecified"))
    )
    (net (code "84") (name "T29") (class "Default")
      (node (ref "K30") (pin "1") (pinfunction "1_1") (pintype "unspecified"))
    )
    (net (code "85") (name "T30") (class "Default")
      (node (ref "K31") (pin "1") (pinfunction "1_1") (pintype "unspecified"))
    )
    (net (code "86") (name "T31") (class "Default")
      (node (ref "K32") (pin "1") (pinfunction "1_1") (pintype "unspecified"))
    )
    (net (code "87") (name "T32") (class "Default")
      (node (ref "K17") (pin "3") (pinfunction "3_3") (pintype "unspecified"))
    )
    (net (code "88") (name "T33") (class "Default")
      (node (ref "K18") (pin "3") (pinfunction "3_3") (pintype "unspecified"))
    )
    (net (code "89") (name "T34") (class "Default")
      (node (ref "K19") (pin "3") (pinfunction "3_3") (pintype "unspecified"))
    )
    (net (code "90") (name "T35") (class "Default")
      (node (ref "K20") (pin "3") (pinfunction "3_3") (pintype "unspecified"))
    )
    (net (code "91") (name "T36") (class "Default")
      (node (ref "K21") (pin "3") (pinfunction "3_3") (pintype "unspecified"))
    )
    (net (code "92") (name "T37") (class "Default")
      (node (ref "K22") (pin "3") (pinfunction "3_3") (pintype "unspecified"))
    )
    (net (code "93") (name "T38") (class "Default")
      (node (ref "K23") (pin "3") (pinfunction "3_3") (pintype "unspecified"))
    )
    (net (code "94") (name "T39") (class "Default")
      (node (ref "K24") (pin "3") (pinfunction "3_3") (pintype "unspecified"))
    )
    (net (code "95") (name "T40") (class "Default")
      (node (ref "K25") (pin "3") (pinfunction "3_3") (pintype "unspecified"))
    )
    (net (code "96") (name "T41") (class "Default")
      (node (ref "K26") (pin "3") (pinfunction "3_3") (pintype "unspecified"))
    )
    (net (code "97") (name "T42") (class "Default")
      (node (ref "K27") (pin "3") (pinfunction "3_3") (pintype "unspecified"))
    )
    (net (code "98") (name "T43") (class "Default")
      (node (ref "K28") (pin "3") (pinfunction "3_3") (pintype "unspecified"))
    )
    (net (code "99") (name "T44") (class "Default")
      (node (ref "K29") (pin "3") (pinfunction "3_3") (pintype "unspecified"))
    )
    (net (code "100") (name "T45") (class "Default")
      (node (ref "K30") (pin "3") (pinfunction "3_3") (pintype "unspecified"))
    )
    (net (code "101") (name "T46") (class "Default")
      (node (ref "K31") (pin "3") (pinfunction "3_3") (pintype "unspecified"))
    )
    (net (code "102") (name "T47") (class "Default")
      (node (ref "K32") (pin "3") (pinfunction "3_3") (pintype "unspecified"))
    )
    (net (code "131") (name "unconnected-(K1-Pad4)") (class "Default")
      (node (ref "K1") (pin "4") (pinfunction "4_4") (pintype "unspecified"))
    )
    (net (code "132") (name "unconnected-(K2-Pad4)") (class "Default")
      (node (ref "K2") (pin "4") (pinfunction "4_4") (pintype "unspecified"))
    )
    (net (code "133") (name "unconnected-(K3-Pad4)") (class "Default")
      (node (ref "K3") (pin "4") (pinfunction "4_4") (pintype "unspecified"))
    )
    (net (code "134") (name "unconnected-(K4-Pad4)") (class "Default")
      (node (ref "K4") (pin "4") (pinfunction "4_4") (pintype "unspecified"))
    )
    (net (code "135") (name "unconnected-(K5-Pad4)") (class "Default")
      (node (ref "K5") (pin "4") (pinfunction "4_4") (pintype "unspecified"))
    )
    (net (code "136") (name "unconnected-(K6-Pad4)") (class "Default")
      (node (ref "K6") (pin "4") (pinfunction "4_4") (pintype "unspecified"))
    )
    (net (code "137") (name "unconnected-(K7-Pad4)") (class "Default")
      (node (ref "K7") (pin "4") (pinfunction "4_4") (pintype "unspecified"))
    )
    (net (code "138") (name "unconnected-(K8-Pad4)") (class "Default")
      (node (ref "K8") (pin "4") (pinfunction "4_4") (pintype "unspecified"))
    )
    (net (code "139") (name "unconnected-(K9-Pad4)") (class "Default")
      (node (ref "K9") (pin "4") (pinfunction "4_4") (pintype "unspecified"))
    )
    (net (code "140") (name "unconnected-(K10-Pad4)") (class "Default")
      (node (ref "K10") (pin "4") (pinfunction "4_4") (pintype "unspecified"))
    )
    (net (code "141") (name "unconnected-(K11-Pad4)") (class "Default")
      (node (ref "K11") (pin "4") (pinfunction "4_4") (pintype "unspecified"))
    )
    (net (code "142") (name "unconnected-(K12-Pad4)") (class "Default")
      (node (ref "K12") (pin "4") (pinfunction "4_4") (pintype "unspecified"))
    )
    (net (code "143") (name "unconnected-(K13-Pad4)") (class "Default")
      (node (ref "K13") (pin "4") (pinfunction "4_4") (pintype "unspecified"))
    )
    (net (code "144") (name "unconnected-(K14-Pad4)") (class "Default")
      (node (ref "K14") (pin "4") (pinfunction "4_4") (pintype "unspecified"))
    )
    (net (code "145") (name "unconnected-(K15-Pad4)") (class "Default")
      (node (ref "K15") (pin "4") (pinfunction "4_4") (pintype "unspecified"))
    )
    (net (code "146") (name "unconnected-(K16-Pad4)") (class "Default")
      (node (ref "K16") (pin "4") (pinfunction "4_4") (pintype "unspecified"))
    )
    (net (code "147") (name "unconnected-(K17-Pad4)") (class "Default")
      (node (ref "K17") (pin "4") (pinfunction "4_4") (pintype "unspecified"))
    )
    (net (code "148") (name "unconnected-(K18-Pad4)") (class "Default")
      (node (ref "K18") (pin "4") (pinfunction "4_4") (pintype "unspecified"))
    )
    (net (code "149") (name "unconnected-(K19-Pad4)") (class "Default")
      (node (ref "K19") (pin "4") (pinfunction "4_4") (pintype "unspecified"))
    )
    (net (code "150") (name "unconnected-(K19-Pad5)") (class "Default")
      (node (ref "K19") (pin "5") (pinfunction "5_5") (pintype "unspecified"))
    )
    (net (code "151") (name "unconnected-(K20-Pad4)") (class "Default")
      (node (ref "K20") (pin "4") (pinfunction "4_4") (pintype "unspecified"))
    )
    (net (code "152") (name "unconnected-(K21-Pad4)") (class "Default")
      (node (ref "K21") (pin "4") (pinfunction "4_4") (pintype "unspecified"))
    )
    (net (code "153") (name "unconnected-(K22-Pad4)") (class "Default")
      (node (ref "K22") (pin "4") (pinfunction "4_4") (pintype "unspecified"))
    )
    (net (code "154") (name "unconnected-(K23-Pad4)") (class "Default")
      (node (ref "K23") (pin "4") (pinfunction "4_4") (pintype "unspecified"))
    )
    (net (code "155") (name "unconnected-(K24-Pad4)") (class "Default")
      (node (ref "K24") (pin "4") (pinfunction "4_4") (pintype "unspecified"))
    )
    (net (code "156") (name "unconnected-(K25-Pad4)") (class "Default")
      (node (ref "K25") (pin "4") (pinfunction "4_4") (pintype "unspecified"))
    )
    (net (code "157") (name "unconnected-(K26-Pad4)") (class "Default")
      (node (ref "K26") (pin "4") (pinfunction "4_4") (pintype "unspecified"))
    )
    (net (code "158") (name "unconnected-(K27-Pad4)") (class "Default")
      (node (ref "K27") (pin "4") (pinfunction "4_4") (pintype "unspecified"))
    )
    (net (code "159") (name "unconnected-(K28-Pad4)") (class "Default")
      (node (ref "K28") (pin "4") (pinfunction "4_4") (pintype "unspecified"))
    )
    (net (code "160") (name "unconnected-(K29-Pad4)") (class "Default")
      (node (ref "K29") (pin "4") (pinfunction "4_4") (pintype "unspecified"))
    )
    (net (code "161") (name "unconnected-(K30-Pad4)") (class "Default")
      (node (ref "K30") (pin "4") (pinfunction "4_4") (pintype "unspecified"))
    )
    (net (code "162") (name "unconnected-(K31-Pad4)") (class "Default")
      (node (ref "K31") (pin "4") (pinfunction "4_4") (pintype "unspecified"))
    )
    (net (code "163") (name "unconnected-(K32-Pad4)") (class "Default")
      (node (ref "K32") (pin "4") (pinfunction "4_4") (pintype "unspecified"))
    )
    (net (code "164") (name "unconnected-(KEY15-Pad2)") (class "Default")
      (node (ref "KEY15") (pin "2") (pinfunction "2_2") (pintype "unspecified"))
    )
    (net (code "165") (name "unconnected-(KEY16-Pad2)") (class "Default")
      (node (ref "KEY16") (pin "2") (pinfunction "2_2") (pintype "unspecified"))
    )
    (net (code "166") (name "unconnected-(SW1-Pad1)") (class "Default")
      (node (ref "SW1") (pin "1") (pinfunction "1_1") (pintype "unspecified"))
    )
    (net (code "167") (name "unconnected-(SW1-Pad2)") (class "Default")
      (node (ref "SW1") (pin "2") (pinfunction "2_2") (pintype "unspecified"))
    )
    (net (code "168") (name "unconnected-(SW1-Pad3)") (class "Default")
      (node (ref "SW1") (pin "3") (pinfunction "3_3") (pintype "unspecified"))
    )
    (net (code "169") (name "unconnected-(SW1-Pad4)") (class "Default")
      (node (ref "SW1") (pin "4") (pinfunction "4_4") (pintype "unspecified"))
    )
    (net (code "170") (name "unconnected-(SW1-Pad5)") (class "Default")
      (node (ref "SW1") (pin "5") (pinfunction "5_5") (pintype "unspecified"))
    )
    (net (code "171") (name "unconnected-(U1-0V-Pad76)") (class "Default")
      (node (ref "U1") (pin "76") (pinfunction "0V_76") (pintype "unspecified"))
    )
    (net (code "172") (name "unconnected-(U1-A00-Pad2)") (class "Default")
      (node (ref "U1") (pin "2") (pinfunction "A00_2") (pintype "unspecified"))
    )
    (net (code "173") (name "unconnected-(U1-A01-Pad4)") (class "Default")
      (node (ref "U1") (pin "4") (pinfunction "A01_4") (pintype "unspecified"))
    )
    (net (code "174") (name "unconnected-(U1-A02-Pad6)") (class "Default")
      (node (ref "U1") (pin "6") (pinfunction "A02_6") (pintype "unspecified"))
    )
    (net (code "175") (name "unconnected-(U1-A03-Pad8)") (class "Default")
      (node (ref "U1") (pin "8") (pinfunction "A03_8") (pintype "unspecified"))
    )
    (net (code "176") (name "unconnected-(U1-AI0.I-Pad67)") (class "Default")
      (node (ref "U1") (pin "67") (pinfunction "AI0.I_67") (pintype "unspecified"))
    )
    (net (code "177") (name "unconnected-(U1-AI0.V-Pad66)") (class "Default")
      (node (ref "U1") (pin "66") (pinfunction "AI0.V_66") (pintype "unspecified"))
    )
    (net (code "178") (name "unconnected-(U1-AI1.I-Pad64)") (class "Default")
      (node (ref "U1") (pin "64") (pinfunction "AI1.I_64") (pintype "unspecified"))
    )
    (net (code "179") (name "unconnected-(U1-AI1.V-Pad63)") (class "Default")
      (node (ref "U1") (pin "63") (pinfunction "AI1.V_63") (pintype "unspecified"))
    )
    (net (code "180") (name "unconnected-(U1-AI2.I-Pad61)") (class "Default")
      (node (ref "U1") (pin "61") (pinfunction "AI2.I_61") (pintype "unspecified"))
    )
    (net (code "181") (name "unconnected-(U1-AI2.V-Pad60)") (class "Default")
      (node (ref "U1") (pin "60") (pinfunction "AI2.V_60") (pintype "unspecified"))
    )
    (net (code "182") (name "unconnected-(U1-AI3.I-Pad58)") (class "Default")
      (node (ref "U1") (pin "58") (pinfunction "AI3.I_58") (pintype "unspecified"))
    )
    (net (code "183") (name "unconnected-(U1-AI3.V-Pad57)") (class "Default")
      (node (ref "U1") (pin "57") (pinfunction "AI3.V_57") (pintype "unspecified"))
    )
    (net (code "184") (name "unconnected-(U1-AI4.I-Pad55)") (class "Default")
      (node (ref "U1") (pin "55") (pinfunction "AI4.I_55") (pintype "unspecified"))
    )
    (net (code "185") (name "unconnected-(U1-AI4.V-Pad54)") (class "Default")
      (node (ref "U1") (pin "54") (pinfunction "AI4.V_54") (pintype "unspecified"))
    )
    (net (code "186") (name "unconnected-(U1-C0-Pad53)") (class "Default")
      (node (ref "U1") (pin "53") (pinfunction "C0_53") (pintype "unspecified"))
    )
    (net (code "187") (name "unconnected-(U1-C1-Pad44)") (class "Default")
      (node (ref "U1") (pin "44") (pinfunction "C1_44") (pintype "unspecified"))
    )
    (net (code "188") (name "unconnected-(U1-C2-Pad56)") (class "Default")
      (node (ref "U1") (pin "56") (pinfunction "C2_56") (pintype "unspecified"))
    )
    (net (code "189") (name "unconnected-(U1-C2-Pad59)") (class "Default")
      (node (ref "U1") (pin "59") (pinfunction "C2_59") (pintype "unspecified"))
    )
    (net (code "190") (name "unconnected-(U1-C2-Pad62)") (class "Default")
      (node (ref "U1") (pin "62") (pinfunction "C2_62") (pintype "unspecified"))
    )
    (net (code "191") (name "unconnected-(U1-C2-Pad65)") (class "Default")
      (node (ref "U1") (pin "65") (pinfunction "C2_65") (pintype "unspecified"))
    )
    (net (code "192") (name "unconnected-(U1-C2-Pad68)") (class "Default")
      (node (ref "U1") (pin "68") (pinfunction "C2_68") (pintype "unspecified"))
    )
    (net (code "193") (name "unconnected-(U1-C3-Pad1)") (class "Default")
      (node (ref "U1") (pin "1") (pinfunction "C3_1") (pintype "unspecified"))
    )
    (net (code "194") (name "unconnected-(U1-C3-Pad3)") (class "Default")
      (node (ref "U1") (pin "3") (pinfunction "C3_3") (pintype "unspecified"))
    )
    (net (code "195") (name "unconnected-(U1-C3-Pad5)") (class "Default")
      (node (ref "U1") (pin "5") (pinfunction "C3_5") (pintype "unspecified"))
    )
    (net (code "196") (name "unconnected-(U1-C3-Pad7)") (class "Default")
      (node (ref "U1") (pin "7") (pinfunction "C3_7") (pintype "unspecified"))
    )
    (net (code "197") (name "unconnected-(U1-D+-Pad30)") (class "Default")
      (node (ref "U1") (pin "30") (pinfunction "D+_30") (pintype "unspecified"))
    )
    (net (code "198") (name "unconnected-(U1-D--Pad31)") (class "Default")
      (node (ref "U1") (pin "31") (pinfunction "D-_31") (pintype "unspecified"))
    )
    (net (code "199") (name "unconnected-(U1-GND-Pad29)") (class "Default")
      (node (ref "U1") (pin "29") (pinfunction "GND_29") (pintype "unspecified"))
    )
    (net (code "200") (name "unconnected-(U1-GND-Pad32)") (class "Default")
      (node (ref "U1") (pin "32") (pinfunction "GND_32") (pintype "unspecified"))
    )
    (net (code "201") (name "unconnected-(U1-GND-Pad35)") (class "Default")
      (node (ref "U1") (pin "35") (pinfunction "GND_35") (pintype "unspecified"))
    )
    (net (code "202") (name "unconnected-(U1-GND-Pad77)") (class "Default")
      (node (ref "U1") (pin "77") (pinfunction "GND_77") (pintype "unspecified"))
    )
    (net (code "203") (name "unconnected-(U1-H-Pad33)") (class "Default")
      (node (ref "U1") (pin "33") (pinfunction "H_33") (pintype "unspecified"))
    )
    (net (code "204") (name "unconnected-(U1-I00-Pad52)") (class "Default")
      (node (ref "U1") (pin "52") (pinfunction "I00_52") (pintype "unspecified"))
    )
    (net (code "205") (name "unconnected-(U1-I01-Pad51)") (class "Default")
      (node (ref "U1") (pin "51") (pinfunction "I01_51") (pintype "unspecified"))
    )
    (net (code "206") (name "unconnected-(U1-I02-Pad50)") (class "Default")
      (node (ref "U1") (pin "50") (pinfunction "I02_50") (pintype "unspecified"))
    )
    (net (code "207") (name "unconnected-(U1-I03-Pad49)") (class "Default")
      (node (ref "U1") (pin "49") (pinfunction "I03_49") (pintype "unspecified"))
    )
    (net (code "208") (name "unconnected-(U1-I04-Pad48)") (class "Default")
      (node (ref "U1") (pin "48") (pinfunction "I04_48") (pintype "unspecified"))
    )
    (net (code "209") (name "unconnected-(U1-I05-Pad47)") (class "Default")
      (node (ref "U1") (pin "47") (pinfunction "I05_47") (pintype "unspecified"))
    )
    (net (code "210") (name "unconnected-(U1-I06-Pad46)") (class "Default")
      (node (ref "U1") (pin "46") (pinfunction "I06_46") (pintype "unspecified"))
    )
    (net (code "211") (name "unconnected-(U1-I07-Pad45)") (class "Default")
      (node (ref "U1") (pin "45") (pinfunction "I07_45") (pintype "unspecified"))
    )
    (net (code "212") (name "unconnected-(U1-I10-Pad43)") (class "Default")
      (node (ref "U1") (pin "43") (pinfunction "I10_43") (pintype "unspecified"))
    )
    (net (code "213") (name "unconnected-(U1-I11-Pad42)") (class "Default")
      (node (ref "U1") (pin "42") (pinfunction "I11_42") (pintype "unspecified"))
    )
    (net (code "214") (name "unconnected-(U1-I12-Pad41)") (class "Default")
      (node (ref "U1") (pin "41") (pinfunction "I12_41") (pintype "unspecified"))
    )
    (net (code "215") (name "unconnected-(U1-I13-Pad40)") (class "Default")
      (node (ref "U1") (pin "40") (pinfunction "I13_40") (pintype "unspecified"))
    )
    (net (code "216") (name "unconnected-(U1-I14-Pad39)") (class "Default")
      (node (ref "U1") (pin "39") (pinfunction "I14_39") (pintype "unspecified"))
    )
    (net (code "217") (name "unconnected-(U1-I15-Pad38)") (class "Default")
      (node (ref "U1") (pin "38") (pinfunction "I15_38") (pintype "unspecified"))
    )
    (net (code "218") (name "unconnected-(U1-I16-Pad37)") (class "Default")
      (node (ref "U1") (pin "37") (pinfunction "I16_37") (pintype "unspecified"))
    )
    (net (code "219") (name "unconnected-(U1-I17-Pad36)") (class "Default")
      (node (ref "U1") (pin "36") (pinfunction "I17_36") (pintype "unspecified"))
    )
    (net (code "220") (name "unconnected-(U1-L-Pad34)") (class "Default")
      (node (ref "U1") (pin "34") (pinfunction "L_34") (pintype "unspecified"))
    )
    (net (code "221") (name "unconnected-(U1-Q+-Pad27)") (class "Default")
      (node (ref "U1") (pin "27") (pinfunction "Q+_27") (pintype "unspecified"))
    )
    (net (code "222") (name "unconnected-(U1-Q+-Pad28)") (class "Default")
      (node (ref "U1") (pin "28") (pinfunction "Q+_28") (pintype "unspecified"))
    )
    (net (code "223") (name "unconnected-(U1-Q--Pad9)") (class "Default")
      (node (ref "U1") (pin "9") (pinfunction "Q-_9") (pintype "unspecified"))
    )
    (net (code "224") (name "unconnected-(U1-Q00-Pad10)") (class "Default")
      (node (ref "U1") (pin "10") (pinfunction "Q00_10") (pintype "unspecified"))
    )
    (net (code "225") (name "unconnected-(U1-Q01-Pad11)") (class "Default")
      (node (ref "U1") (pin "11") (pinfunction "Q01_11") (pintype "unspecified"))
    )
    (net (code "226") (name "unconnected-(U1-Q02-Pad12)") (class "Default")
      (node (ref "U1") (pin "12") (pinfunction "Q02_12") (pintype "unspecified"))
    )
    (net (code "227") (name "unconnected-(U1-Q03-Pad13)") (class "Default")
      (node (ref "U1") (pin "13") (pinfunction "Q03_13") (pintype "unspecified"))
    )
    (net (code "228") (name "unconnected-(U1-Q04-Pad14)") (class "Default")
      (node (ref "U1") (pin "14") (pinfunction "Q04_14") (pintype "unspecified"))
    )
    (net (code "229") (name "unconnected-(U1-Q05-Pad15)") (class "Default")
      (node (ref "U1") (pin "15") (pinfunction "Q05_15") (pintype "unspecified"))
    )
    (net (code "230") (name "unconnected-(U1-Q06-Pad17)") (class "Default")
      (node (ref "U1") (pin "17") (pinfunction "Q06_17") (pintype "unspecified"))
    )
    (net (code "231") (name "unconnected-(U1-Q07-Pad18)") (class "Default")
      (node (ref "U1") (pin "18") (pinfunction "Q07_18") (pintype "unspecified"))
    )
    (net (code "232") (name "unconnected-(U1-Q10-Pad19)") (class "Default")
      (node (ref "U1") (pin "19") (pinfunction "Q10_19") (pintype "unspecified"))
    )
    (net (code "233") (name "unconnected-(U1-Q11-Pad20)") (class "Default")
      (node (ref "U1") (pin "20") (pinfunction "Q11_20") (pintype "unspecified"))
    )
    (net (code "234") (name "unconnected-(U1-Q12-Pad21)") (class "Default")
      (node (ref "U1") (pin "21") (pinfunction "Q12_21") (pintype "unspecified"))
    )
    (net (code "235") (name "unconnected-(U1-Q13-Pad22)") (class "Default")
      (node (ref "U1") (pin "22") (pinfunction "Q13_22") (pintype "unspecified"))
    )
    (net (code "236") (name "unconnected-(U1-Q14-Pad23)") (class "Default")
      (node (ref "U1") (pin "23") (pinfunction "Q14_23") (pintype "unspecified"))
    )
    (net (code "237") (name "unconnected-(U1-Q15-Pad24)") (class "Default")
      (node (ref "U1") (pin "24") (pinfunction "Q15_24") (pintype "unspecified"))
    )
    (net (code "238") (name "unconnected-(U1-Q16-Pad25)") (class "Default")
      (node (ref "U1") (pin "25") (pinfunction "Q16_25") (pintype "unspecified"))
    )
    (net (code "239") (name "unconnected-(U1-Q17-Pad26)") (class "Default")
      (node (ref "U1") (pin "26") (pinfunction "Q17_26") (pintype "unspecified"))
    )
    (net (code "240") (name "unconnected-(U1-RI0.A-Pad72)") (class "Default")
      (node (ref "U1") (pin "72") (pinfunction "RI0.A_72") (pintype "unspecified"))
    )
    (net (code "241") (name "unconnected-(U1-RI0.B-Pad73)") (class "Default")
      (node (ref "U1") (pin "73") (pinfunction "RI0.B_73") (pintype "unspecified"))
    )
    (net (code "242") (name "unconnected-(U1-RI0.C-Pad74)") (class "Default")
      (node (ref "U1") (pin "74") (pinfunction "RI0.C_74") (pintype "unspecified"))
    )
    (net (code "243") (name "unconnected-(U1-RI1.A-Pad69)") (class "Default")
      (node (ref "U1") (pin "69") (pinfunction "RI1.A_69") (pintype "unspecified"))
    )
    (net (code "244") (name "unconnected-(U1-RI1.B-Pad70)") (class "Default")
      (node (ref "U1") (pin "70") (pinfunction "RI1.B_70") (pintype "unspecified"))
    )
    (net (code "245") (name "unconnected-(U1-RI1.C-Pad71)") (class "Default")
      (node (ref "U1") (pin "71") (pinfunction "RI1.C_71") (pintype "unspecified"))
    )
    (net (code "246") (name "unconnected-(U1-V+-Pad75)") (class "Default")
      (node (ref "U1") (pin "75") (pinfunction "V+_75") (pintype "unspecified"))
    )
    (net (code "247") (name "unconnected-(U2-GND-Pad7)") (class "Default")
      (node (ref "U2") (pin "7") (pinfunction "GND_7") (pintype "unspecified"))
    )
    (net (code "248") (name "unconnected-(U2-L-Pad5)") (class "Default")
      (node (ref "U2") (pin "5") (pinfunction "L_5") (pintype "unspecified"))
    )
    (net (code "249") (name "unconnected-(U2-N-Pad6)") (class "Default")
      (node (ref "U2") (pin "6") (pinfunction "N_6") (pintype "unspecified"))
    )
    (net (code "250") (name "unconnected-(U2-V+-Pad1)") (class "Default")
      (node (ref "U2") (pin "1") (pinfunction "V+_1") (pintype "unspecified"))
    )
    (net (code "251") (name "unconnected-(U2-V+-Pad2)") (class "Default")
      (node (ref "U2") (pin "2") (pinfunction "V+_2") (pintype "unspecified"))
    )
    (net (code "252") (name "unconnected-(U2-V--Pad3)") (class "Default")
      (node (ref "U2") (pin "3") (pinfunction "V-_3") (pintype "unspecified"))
    )
    (net (code "253") (name "unconnected-(U2-V--Pad4)") (class "Default")
      (node (ref "U2") (pin "4") (pinfunction "V-_4") (pintype "unspecified"))
    )
  )
)
